# 18_RK3568_VO_Interface_2.net
KiCad netlist of a schematic drawn in Altium Designer
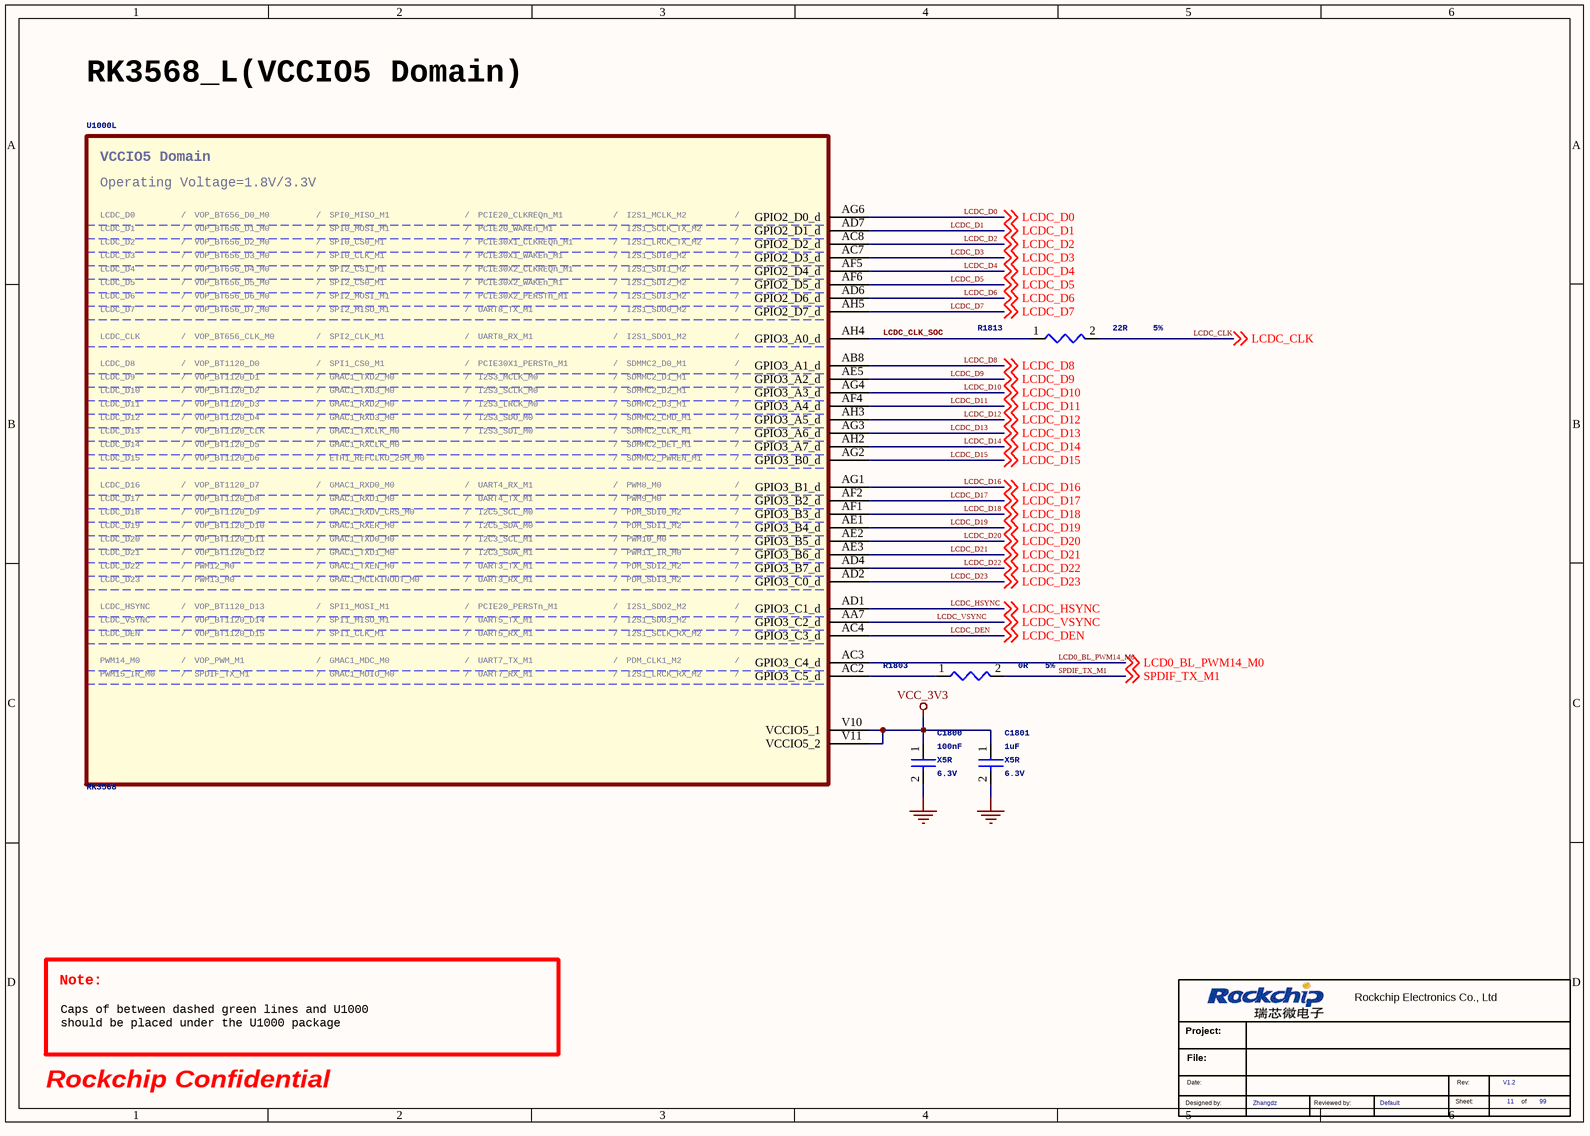
[diagram p0: 18.RK3568_VO Interface_2.SchDoc]

(export (version "E")
  (design (tool "Eeschema 10.0.6"))
  (components
    (comp (ref "*")
      (value "Rockchip_new")
      (fields
        (field (name "SCHEMATIC PAGE COUNT") "99")
        (field (name "SCHEMATIC PAGE NUMBER") "11")
        (field (name "DESIGNER") "Zhangdz")
        (field (name "REVISION") "V1.2")
        (field (name "CHECK") "Default")
      )
      (libsource (lib "*") (part "Rockchip_new"))
    )
    (comp (ref "C1800")
      (value "100nF")
      (footprint "C0201")
      (description "cap,100.00nF,+/-10%,6.3V,X5R,C0201")
      (fields
        (field (name "VOLTAGE") "6.3V")
        (field (name "DIELECTRIC") "X5R")
        (field (name "TOLERANCE") "10%")
        (field (name "MANUFACTURER") "TDK")
        (field (name "CREATED BY") "JJJ")
      )
      (libsource (lib "*") (part "CAP NP"))
    )
    (comp (ref "C1801")
      (value "1uF")
      (footprint "C0402")
      (description "cap,1.00uF,+/-10%,6.3V,X5R,C0402")
      (fields
        (field (name "VOLTAGE") "6.3V")
        (field (name "DIELECTRIC") "X5R")
        (field (name "MANUFACTURER") "TDK")
        (field (name "TOLERANCE") "10%")
        (field (name "CREATED BY") "JJJ")
      )
      (libsource (lib "*") (part "CAP NP"))
    )
    (comp (ref "R1803")
      (value "0R")
      (footprint "R0402")
      (description "通用厚膜电阻,0R,+/-5%,R0402,1/16W.")
      (fields
        (field (name "TOLERANCE") "5%")
        (field (name "MANUFACTURER") "YAGEO")
        (field (name "CREATED BY") "YTL")
      )
      (libsource (lib "*") (part "RESISTOR"))
    )
    (comp (ref "R1813")
      (value "22R")
      (footprint "R0402")
      (description "通用厚膜电阻,22R,+/-5%,R0402,1/16W.")
      (fields
        (field (name "TOLERANCE") "5%")
        (field (name "MANUFACTURER") "YAGEO")
        (field (name "CREATED BY") "YTL")
      )
      (libsource (lib "*") (part "RESISTOR"))
    )
    (comp (ref "U1000")
      (value "RK3568")
      (footprint "BGA636_19R00X19R00X1R20")
      (description "ROCKCHIP SOC")
      (fields (field (name "MANUFACTURER") "Rockchip (瑞芯微)") (field (name "CREATED BY") "JJJ"))
      (libsource (lib "*") (part "SOC_RK3568"))
    )
  )
  (nets
    (net (code "1") (name "/LCDC_CLK_SOC") (class "Default")
      (node (ref "R1813") (pin "1") (pinfunction "1_1") (pintype "passive"))
      (node (ref "U1000") (pin "AH4") (pinfunction "GPIO3_A0_d_AH4") (pintype "passive"))
    )
    (net (code "2") (name "GND") (class "Default")
      (node (ref "C1800") (pin "2") (pinfunction "2_2") (pintype "passive"))
      (node (ref "C1801") (pin "2") (pinfunction "2_2") (pintype "passive"))
    )
    (net (code "3") (name "LCD0_BL_PWM14_M0") (class "Default")
      (node (ref "U1000") (pin "AC3") (pinfunction "GPIO3_C4_d_AC3") (pintype "passive"))
    )
    (net (code "4") (name "LCDC_CLK") (class "Default")
      (node (ref "R1813") (pin "2") (pinfunction "2_2") (pintype "passive"))
    )
    (net (code "5") (name "LCDC_D0") (class "Default")
      (node (ref "U1000") (pin "AG6") (pinfunction "GPIO2_D0_d_AG6") (pintype "passive"))
    )
    (net (code "6") (name "LCDC_D1") (class "Default")
      (node (ref "U1000") (pin "AD7") (pinfunction "GPIO2_D1_d_AD7") (pintype "passive"))
    )
    (net (code "7") (name "LCDC_D2") (class "Default")
      (node (ref "U1000") (pin "AC8") (pinfunction "GPIO2_D2_d_AC8") (pintype "passive"))
    )
    (net (code "8") (name "LCDC_D3") (class "Default")
      (node (ref "U1000") (pin "AC7") (pinfunction "GPIO2_D3_d_AC7") (pintype "passive"))
    )
    (net (code "9") (name "LCDC_D4") (class "Default")
      (node (ref "U1000") (pin "AF5") (pinfunction "GPIO2_D4_d_AF5") (pintype "passive"))
    )
    (net (code "10") (name "LCDC_D5") (class "Default")
      (node (ref "U1000") (pin "AF6") (pinfunction "GPIO2_D5_d_AF6") (pintype "passive"))
    )
    (net (code "11") (name "LCDC_D6") (class "Default")
      (node (ref "U1000") (pin "AD6") (pinfunction "GPIO2_D6_d_AD6") (pintype "passive"))
    )
    (net (code "12") (name "LCDC_D7") (class "Default")
      (node (ref "U1000") (pin "AH5") (pinfunction "GPIO2_D7_d_AH5") (pintype "passive"))
    )
    (net (code "13") (name "LCDC_D8") (class "Default")
      (node (ref "U1000") (pin "AB8") (pinfunction "GPIO3_A1_d_AB8") (pintype "passive"))
    )
    (net (code "14") (name "LCDC_D9") (class "Default")
      (node (ref "U1000") (pin "AE5") (pinfunction "GPIO3_A2_d_AE5") (pintype "passive"))
    )
    (net (code "15") (name "LCDC_D10") (class "Default")
      (node (ref "U1000") (pin "AG4") (pinfunction "GPIO3_A3_d_AG4") (pintype "passive"))
    )
    (net (code "16") (name "LCDC_D11") (class "Default")
      (node (ref "U1000") (pin "AF4") (pinfunction "GPIO3_A4_d_AF4") (pintype "passive"))
    )
    (net (code "17") (name "LCDC_D12") (class "Default")
      (node (ref "U1000") (pin "AH3") (pinfunction "GPIO3_A5_d_AH3") (pintype "passive"))
    )
    (net (code "18") (name "LCDC_D13") (class "Default")
      (node (ref "U1000") (pin "AG3") (pinfunction "GPIO3_A6_d_AG3") (pintype "passive"))
    )
    (net (code "19") (name "LCDC_D14") (class "Default")
      (node (ref "U1000") (pin "AH2") (pinfunction "GPIO3_A7_d_AH2") (pintype "passive"))
    )
    (net (code "20") (name "LCDC_D15") (class "Default")
      (node (ref "U1000") (pin "AG2") (pinfunction "GPIO3_B0_d_AG2") (pintype "passive"))
    )
    (net (code "21") (name "LCDC_D16") (class "Default")
      (node (ref "U1000") (pin "AG1") (pinfunction "GPIO3_B1_d_AG1") (pintype "passive"))
    )
    (net (code "22") (name "LCDC_D17") (class "Default")
      (node (ref "U1000") (pin "AF2") (pinfunction "GPIO3_B2_d_AF2") (pintype "passive"))
    )
    (net (code "23") (name "LCDC_D18") (class "Default")
      (node (ref "U1000") (pin "AF1") (pinfunction "GPIO3_B3_d_AF1") (pintype "passive"))
    )
    (net (code "24") (name "LCDC_D19") (class "Default")
      (node (ref "U1000") (pin "AE1") (pinfunction "GPIO3_B4_d_AE1") (pintype "passive"))
    )
    (net (code "25") (name "LCDC_D20") (class "Default")
      (node (ref "U1000") (pin "AE2") (pinfunction "GPIO3_B5_d_AE2") (pintype "passive"))
    )
    (net (code "26") (name "LCDC_D21") (class "Default")
      (node (ref "U1000") (pin "AE3") (pinfunction "GPIO3_B6_d_AE3") (pintype "passive"))
    )
    (net (code "27") (name "LCDC_D22") (class "Default")
      (node (ref "U1000") (pin "AD4") (pinfunction "GPIO3_B7_d_AD4") (pintype "passive"))
    )
    (net (code "28") (name "LCDC_D23") (class "Default")
      (node (ref "U1000") (pin "AD2") (pinfunction "GPIO3_C0_d_AD2") (pintype "passive"))
    )
    (net (code "29") (name "LCDC_DEN") (class "Default")
      (node (ref "U1000") (pin "AC4") (pinfunction "GPIO3_C3_d_AC4") (pintype "passive"))
    )
    (net (code "30") (name "LCDC_HSYNC") (class "Default")
      (node (ref "U1000") (pin "AD1") (pinfunction "GPIO3_C1_d_AD1") (pintype "passive"))
    )
    (net (code "31") (name "LCDC_VSYNC") (class "Default")
      (node (ref "U1000") (pin "AA7") (pinfunction "GPIO3_C2_d_AA7") (pintype "passive"))
    )
    (net (code "32") (name "Net-(U1000L-GPIO3_C5_d)") (class "Default")
      (node (ref "R1803") (pin "1") (pinfunction "1_1") (pintype "passive"))
      (node (ref "U1000") (pin "AC2") (pinfunction "GPIO3_C5_d_AC2") (pintype "passive"))
    )
    (net (code "33") (name "SPDIF_TX_M1") (class "Default")
      (node (ref "R1803") (pin "2") (pinfunction "2_2") (pintype "passive"))
    )
    (net (code "34") (name "VCC_3V3") (class "Default")
      (node (ref "C1800") (pin "1") (pinfunction "1_1") (pintype "passive"))
      (node (ref "C1801") (pin "1") (pinfunction "1_1") (pintype "passive"))
      (node (ref "U1000") (pin "V10") (pinfunction "VCCIO5_1_V10") (pintype "passive"))
      (node (ref "U1000") (pin "V11") (pinfunction "VCCIO5_2_V11") (pintype "passive"))
    )
  )
)
